# PSU_Schematic.net
KiCad netlist of a schematic drawn in Altium Designer
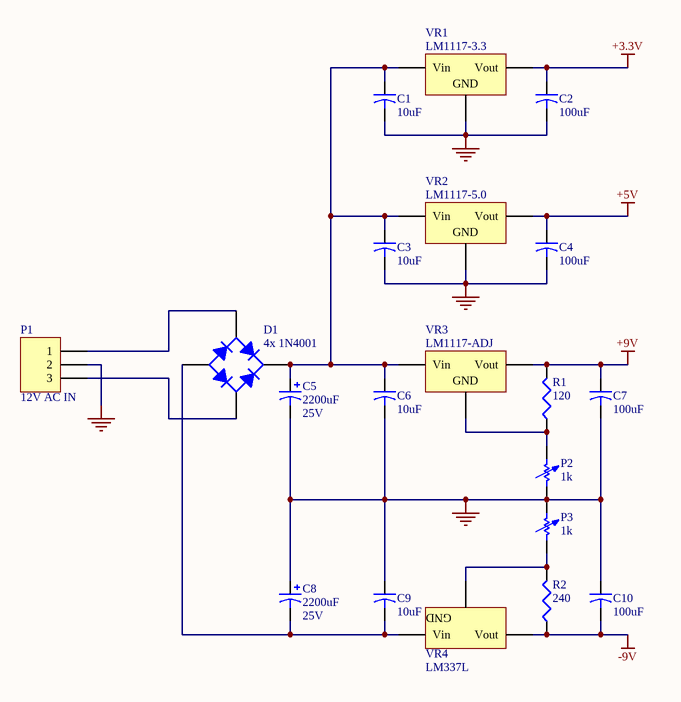
[diagram p0: PSU.Schematic.SchDoc]

(export (version "E")
  (design (tool "Eeschema 10.0.6"))
  (components
    (comp (ref "C1")
      (value "10uF")
      (footprint "CAPC1608N")
      (description "Capacitor")
      (fields (field (name "PUBLISHER") "Altium Limited"))
      (libsource (lib "Miscellaneous Devices") (part "Cap2"))
    )
    (comp (ref "C2")
      (value "100uF")
      (footprint "CAPC1608N")
      (description "Capacitor")
      (fields (field (name "PUBLISHER") "Altium Limited"))
      (libsource (lib "Miscellaneous Devices") (part "Cap2"))
    )
    (comp (ref "C3")
      (value "10uF")
      (footprint "CAPC1608N")
      (description "Capacitor")
      (fields (field (name "PUBLISHER") "Altium Limited"))
      (libsource (lib "Miscellaneous Devices") (part "Cap2"))
    )
    (comp (ref "C4")
      (value "100uF")
      (footprint "CAPC1608N")
      (description "Capacitor")
      (fields (field (name "PUBLISHER") "Altium Limited"))
      (libsource (lib "Miscellaneous Devices") (part "Cap2"))
    )
    (comp (ref "C5")
      (value "2200uF")
      (footprint "CAPC1608N")
      (description "Polarized Capacitor (Radial)")
      (fields (field (name "ALTIUM_VALUE") "25V") (field (name "PUBLISHER") "Altium Limited"))
      (libsource (lib "Miscellaneous Devices") (part "Cap Pol1"))
    )
    (comp (ref "C6")
      (value "10uF")
      (footprint "CAPC1608N")
      (description "Capacitor")
      (fields (field (name "PUBLISHER") "Altium Limited"))
      (libsource (lib "Miscellaneous Devices") (part "Cap2"))
    )
    (comp (ref "C7")
      (value "100uF")
      (footprint "CAPC1608N")
      (description "Capacitor")
      (fields (field (name "PUBLISHER") "Altium Limited"))
      (libsource (lib "Miscellaneous Devices") (part "Cap2"))
    )
    (comp (ref "C8")
      (value "2200uF")
      (footprint "CAPC1608N")
      (description "Polarized Capacitor (Radial)")
      (fields (field (name "ALTIUM_VALUE") "25V") (field (name "PUBLISHER") "Altium Limited"))
      (libsource (lib "Miscellaneous Devices") (part "Cap Pol1"))
    )
    (comp (ref "C9")
      (value "10uF")
      (footprint "CAPC1608N")
      (description "Capacitor")
      (fields (field (name "PUBLISHER") "Altium Limited"))
      (libsource (lib "Miscellaneous Devices") (part "Cap2"))
    )
    (comp (ref "C10")
      (value "100uF")
      (footprint "CAPC1608N")
      (description "Capacitor")
      (fields (field (name "PUBLISHER") "Altium Limited"))
      (libsource (lib "Miscellaneous Devices") (part "Cap2"))
    )
    (comp (ref "D1")
      (value "4x 1N4001")
      (footprint "1N4001")
      (description "Full Wave Diode Bridge")
      (fields (field (name "PUBLISHER") "Altium Limited"))
      (libsource (lib "Miscellaneous Devices") (part "Bridge1"))
    )
    (comp (ref "P1")
      (value "12V AC IN")
      (footprint "HDR1X3")
      (description "Header, 3-Pin")
      (fields (field (name "PUBLISHER") "Altium Limited"))
      (libsource (lib "Miscellaneous Connectors") (part "Header 3"))
    )
    (comp (ref "P2")
      (value "1k")
      (footprint "CAPC1608N")
      (description "Variable Resistor")
      (fields (field (name "PUBLISHER") "Altium Limited"))
      (libsource (lib "Miscellaneous Devices") (part "Res Adj1"))
    )
    (comp (ref "P3")
      (value "1k")
      (footprint "CAPC1608N")
      (description "Variable Resistor")
      (fields (field (name "PUBLISHER") "Altium Limited"))
      (libsource (lib "Miscellaneous Devices") (part "Res Adj1"))
    )
    (comp (ref "R1")
      (value "120")
      (footprint "CAPC1608N")
      (description "Resistor")
      (fields (field (name "PUBLISHER") "Altium Limited"))
      (libsource (lib "Miscellaneous Devices") (part "Res3"))
    )
    (comp (ref "R2")
      (value "240")
      (footprint "CAPC1608N")
      (description "Resistor")
      (fields (field (name "PUBLISHER") "Altium Limited"))
      (libsource (lib "Miscellaneous Devices") (part "Res3"))
    )
    (comp (ref "VR1")
      (value "LM1117-3.3")
      (footprint "LM1117")
      (description "Voltage Regulator")
      (fields (field (name "PUBLISHER") "Altium Limited"))
      (libsource (lib "Miscellaneous Devices") (part "Volt Reg"))
    )
    (comp (ref "VR2")
      (value "LM1117-5.0")
      (footprint "LM1117")
      (description "Voltage Regulator")
      (fields (field (name "PUBLISHER") "Altium Limited"))
      (libsource (lib "Miscellaneous Devices") (part "Volt Reg"))
    )
    (comp (ref "VR3")
      (value "LM1117-ADJ")
      (footprint "LM1117")
      (description "Voltage Regulator")
      (fields (field (name "PUBLISHER") "Altium Limited"))
      (libsource (lib "Miscellaneous Devices") (part "Volt Reg"))
    )
    (comp (ref "VR4")
      (value "LM337L")
      (footprint "LM337L")
      (description "Voltage Regulator")
      (fields (field (name "PUBLISHER") "Altium Limited"))
      (libsource (lib "") (part "Volt Reg_1"))
    )
  )
  (nets
    (net (code "1") (name "+3.3V") (class "Default")
      (node (ref "C2") (pin "1") (pinfunction "1_1") (pintype "passive"))
      (node (ref "VR1") (pin "3") (pinfunction "Vout_3") (pintype "passive"))
    )
    (net (code "2") (name "+5V") (class "Default")
      (node (ref "C4") (pin "1") (pinfunction "1_1") (pintype "passive"))
      (node (ref "VR2") (pin "3") (pinfunction "Vout_3") (pintype "passive"))
    )
    (net (code "3") (name "+9V") (class "Default")
      (node (ref "C7") (pin "1") (pinfunction "1_1") (pintype "passive"))
      (node (ref "R1") (pin "2") (pinfunction "2_2") (pintype "passive"))
      (node (ref "VR3") (pin "3") (pinfunction "Vout_3") (pintype "passive"))
    )
    (net (code "4") (name "-9V") (class "Default")
      (node (ref "C10") (pin "2") (pinfunction "2_2") (pintype "passive"))
      (node (ref "R2") (pin "1") (pinfunction "1_1") (pintype "passive"))
      (node (ref "VR4") (pin "3") (pinfunction "Vout_3") (pintype "passive"))
    )
    (net (code "5") (name "GND") (class "Default")
      (node (ref "C1") (pin "2") (pinfunction "2_2") (pintype "passive"))
      (node (ref "C10") (pin "1") (pinfunction "1_1") (pintype "passive"))
      (node (ref "C2") (pin "2") (pinfunction "2_2") (pintype "passive"))
      (node (ref "C3") (pin "2") (pinfunction "2_2") (pintype "passive"))
      (node (ref "C4") (pin "2") (pinfunction "2_2") (pintype "passive"))
      (node (ref "C5") (pin "2") (pinfunction "2_2") (pintype "passive"))
      (node (ref "C6") (pin "2") (pinfunction "2_2") (pintype "passive"))
      (node (ref "C7") (pin "2") (pinfunction "2_2") (pintype "passive"))
      (node (ref "C8") (pin "1") (pinfunction "1_1") (pintype "passive"))
      (node (ref "C9") (pin "1") (pinfunction "1_1") (pintype "passive"))
      (node (ref "P1") (pin "2") (pinfunction "2_2") (pintype "passive"))
      (node (ref "P2") (pin "1") (pinfunction "1_1") (pintype "passive"))
      (node (ref "P3") (pin "2") (pinfunction "2_2") (pintype "passive"))
      (node (ref "VR1") (pin "2") (pinfunction "GND_2") (pintype "passive"))
      (node (ref "VR2") (pin "2") (pinfunction "GND_2") (pintype "passive"))
    )
    (net (code "6") (name "Net-(D1-A)") (class "Default")
      (node (ref "C8") (pin "2") (pinfunction "2_2") (pintype "passive"))
      (node (ref "C9") (pin "2") (pinfunction "2_2") (pintype "passive"))
      (node (ref "D1") (pin "3") (pinfunction "A_3") (pintype "passive"))
      (node (ref "VR4") (pin "1") (pinfunction "Vin_1") (pintype "passive"))
    )
    (net (code "7") (name "Net-(D1-C-Pad2)") (class "Default")
      (node (ref "D1") (pin "2") (pinfunction "C_2") (pintype "passive"))
      (node (ref "P1") (pin "3") (pinfunction "3_3") (pintype "passive"))
    )
    (net (code "8") (name "Net-(D1-C-Pad4)") (class "Default")
      (node (ref "D1") (pin "4") (pinfunction "C_4") (pintype "passive"))
      (node (ref "P1") (pin "1") (pinfunction "1_1") (pintype "passive"))
    )
    (net (code "9") (name "Net-(D1-K)") (class "Default")
      (node (ref "C1") (pin "1") (pinfunction "1_1") (pintype "passive"))
      (node (ref "C3") (pin "1") (pinfunction "1_1") (pintype "passive"))
      (node (ref "C5") (pin "1") (pinfunction "1_1") (pintype "passive"))
      (node (ref "C6") (pin "1") (pinfunction "1_1") (pintype "passive"))
      (node (ref "D1") (pin "1") (pinfunction "K_1") (pintype "passive"))
      (node (ref "VR1") (pin "1") (pinfunction "Vin_1") (pintype "passive"))
      (node (ref "VR2") (pin "1") (pinfunction "Vin_1") (pintype "passive"))
      (node (ref "VR3") (pin "1") (pinfunction "Vin_1") (pintype "passive"))
    )
    (net (code "10") (name "Net-(VR3-GND)") (class "Default")
      (node (ref "P2") (pin "2") (pinfunction "2_2") (pintype "passive"))
      (node (ref "R1") (pin "1") (pinfunction "1_1") (pintype "passive"))
      (node (ref "VR3") (pin "2") (pinfunction "GND_2") (pintype "passive"))
    )
    (net (code "11") (name "Net-(VR4-ADJ)") (class "Default")
      (node (ref "P3") (pin "1") (pinfunction "1_1") (pintype "passive"))
      (node (ref "R2") (pin "2") (pinfunction "2_2") (pintype "passive"))
      (node (ref "VR4") (pin "2") (pinfunction "ADJ_2") (pintype "passive"))
    )
  )
)
